# opamps.net
KiCad netlist of a schematic drawn in Altium Designer
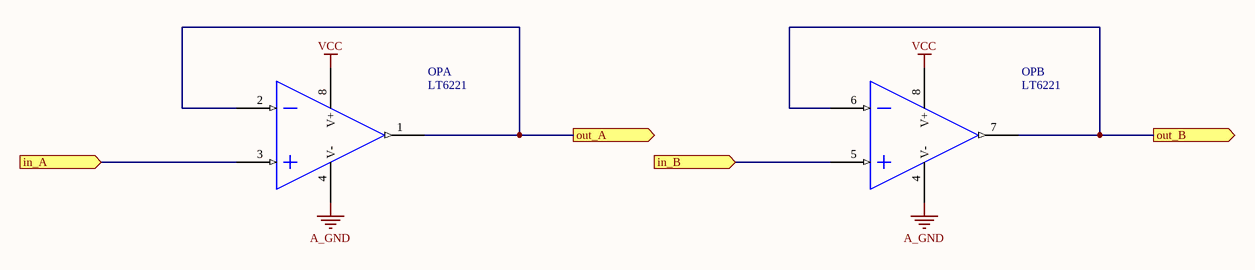
[diagram p0: opamps.SchDoc]

(export (version "E")
  (design (tool "Eeschema 10.0.6"))
  (components (comp (ref "OP") (value "LT6221") (libsource (lib "EceParts") (part "LT6221"))))
  (nets
    (net (code "1") (name "/in_A") (class "Default")
      (node (ref "OP") (pin "3") (pinfunction "IN1(+)_3") (pintype "input"))
    )
    (net (code "2") (name "/in_B") (class "Default")
      (node (ref "OP") (pin "5") (pinfunction "IN2(+)_5") (pintype "input"))
    )
    (net (code "3") (name "/out_A") (class "Default")
      (node (ref "OP") (pin "1") (pinfunction "OUT1_1") (pintype "output"))
      (node (ref "OP") (pin "2") (pinfunction "IN1(-)_2") (pintype "input"))
    )
    (net (code "4") (name "/out_B") (class "Default")
      (node (ref "OP") (pin "6") (pinfunction "IN2(-)_6") (pintype "input"))
      (node (ref "OP") (pin "7") (pinfunction "OUT2_7") (pintype "output"))
    )
    (net (code "5") (name "A_GND") (class "Default")
      (node (ref "OP") (pin "4") (pinfunction "V-_4") (pintype "power_in"))
    )
    (net (code "6") (name "VCC") (class "Default")
      (node (ref "OP") (pin "8") (pinfunction "V+_8") (pintype "power_in"))
    )
  )
)
